# MicroSD.net
KiCad netlist of a schematic drawn in Altium Designer
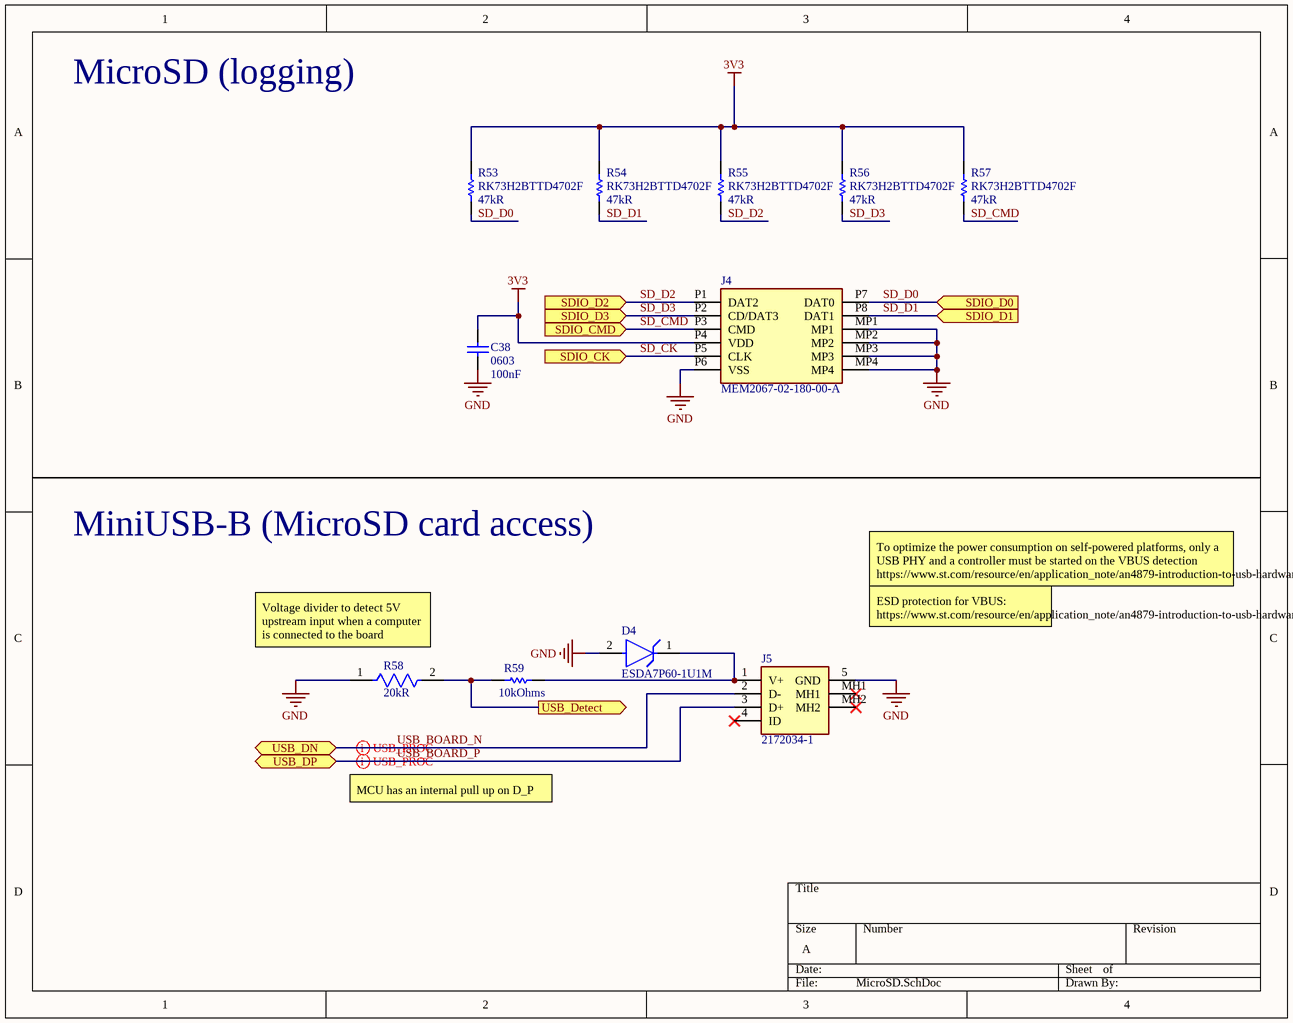
[diagram p0: MicroSD.SchDoc]

(export (version "E")
  (design (tool "Eeschema 10.0.6"))
  (components
    (comp (ref "C38")
      (value "C0603X104K5RACTU")
      (footprint "CAPC1608X87X35NL15T15")
      (fields
        (field (name "MANUFACTURER") "Kemet")
        (field (name "CASE CODE (IMPERIAL)") "0603")
        (field (name "CAPACITANCE") "100nF")
        (field (name "TOLERANCE") "10%")
        (field (name "VOLTAGE") "50V")
      )
      (libsource (lib "Altium Content Vault") (part "CAP"))
    )
    (comp (ref "D4")
      (value "ESDA7P60-1U1M")
      (footprint "FP-1610-MFG")
      (description "TVS DIODE 5V 11.6V 1610")
      (fields
        (field (name "MANUFACTURER") "STMicroelectronics")
        (field (name "OCTOPART") "https://octopart.com/esda7p60-1u1m-stmicroelectronics-52112702")
      )
      (libsource (lib "Altium Content Vault") (part "f813f71cba58e380607f5dd3caf9714"))
    )
    (comp (ref "J4")
      (value "MEM2067-02-180-00-A")
      (footprint "SamacSys:MEM20670218000A")
      (description "Connector")
      (fields (field (name "MOUSER PART NUMBER") "640-MEM20670218000A"))
      (libsource (lib "*") (part "MEM2067-02-180-00-A"))
    )
    (comp (ref "J5")
      (value "2172034-1")
      (footprint "SamacSys:21720341")
      (description "Connector")
      (fields (field (name "MOUSER PART NUMBER") "571-2172034-1"))
      (libsource (lib "*") (part "2172034-1"))
    )
    (comp (ref "R53")
      (value "RK73H2BTTD4702F")
      (footprint "RESC3216X70X40NL20T20")
      (fields (field (name "MANUFACTURER") "KOA Speer") (field (name "ALTIUM_VALUE") "47kR"))
      (libsource (lib "Altium Content Vault") (part "RES"))
    )
    (comp (ref "R54")
      (value "RK73H2BTTD4702F")
      (footprint "RESC3216X70X40NL20T20")
      (fields (field (name "MANUFACTURER") "KOA Speer") (field (name "ALTIUM_VALUE") "47kR"))
      (libsource (lib "Altium Content Vault") (part "RES"))
    )
    (comp (ref "R55")
      (value "RK73H2BTTD4702F")
      (footprint "RESC3216X70X40NL20T20")
      (fields (field (name "MANUFACTURER") "KOA Speer") (field (name "ALTIUM_VALUE") "47kR"))
      (libsource (lib "Altium Content Vault") (part "RES"))
    )
    (comp (ref "R56")
      (value "RK73H2BTTD4702F")
      (footprint "RESC3216X70X40NL20T20")
      (fields (field (name "MANUFACTURER") "KOA Speer") (field (name "ALTIUM_VALUE") "47kR"))
      (libsource (lib "Altium Content Vault") (part "RES"))
    )
    (comp (ref "R57")
      (value "RK73H2BTTD4702F")
      (footprint "RESC3216X70X40NL20T20")
      (fields (field (name "MANUFACTURER") "KOA Speer") (field (name "ALTIUM_VALUE") "47kR"))
      (libsource (lib "Altium Content Vault") (part "RES"))
    )
    (comp (ref "R58")
      (value "CRCW080520K0JNEB")
      (footprint "FP-CRCW0805-e3-IPC_B")
      (description "RES Thick Film, 20kΩ, 5%, 0.125W, 200ppm/°C, 0805")
      (fields (field (name "RESISTANCE") "20kR") (field (name "TOLERANCE") "5%"))
      (libsource (lib "Altium Content Vault") (part "1029c3af85768c4190bb7ad29bc67b5"))
    )
    (comp (ref "R59")
      (value "RC0603JR-0710KL")
      (footprint "RESC1608X55X25ML10T15")
      (description "Resistor, 10 KOhm, +/- 5%, 100 mW, -55 to 155 degC, 0603 (1608 Metric), RoHS, Tape and Reel")
      (fields
        (field (name "RESISTANCE") "10kOhms")
        (field (name "MANUFACTURER") "Yageo")
        (field (name "TOLERANCE") "5%")
      )
      (libsource (lib "Altium Content Vault") (part "RES-2"))
    )
  )
  (nets
    (net (code "1") (name "/SD_CK") (class "Default")
      (node (ref "J4") (pin "P5") (pinfunction "CLK_P5") (pintype "passive"))
    )
    (net (code "2") (name "/SD_CMD") (class "Default")
      (node (ref "J4") (pin "P3") (pinfunction "CMD_P3") (pintype "passive"))
      (node (ref "R57") (pin "1") (pinfunction "1_1") (pintype "passive"))
    )
    (net (code "3") (name "/SD_D0") (class "Default")
      (node (ref "J4") (pin "P7") (pinfunction "DAT0_P7") (pintype "passive"))
      (node (ref "R53") (pin "1") (pinfunction "1_1") (pintype "passive"))
    )
    (net (code "4") (name "/SD_D1") (class "Default")
      (node (ref "J4") (pin "P8") (pinfunction "DAT1_P8") (pintype "passive"))
      (node (ref "R54") (pin "1") (pinfunction "1_1") (pintype "passive"))
    )
    (net (code "5") (name "/SD_D2") (class "Default")
      (node (ref "J4") (pin "P1") (pinfunction "DAT2_P1") (pintype "passive"))
      (node (ref "R55") (pin "1") (pinfunction "1_1") (pintype "passive"))
    )
    (net (code "6") (name "/SD_D3") (class "Default")
      (node (ref "J4") (pin "P2") (pinfunction "CD/DAT3_P2") (pintype "passive"))
      (node (ref "R56") (pin "1") (pinfunction "1_1") (pintype "passive"))
    )
    (net (code "7") (name "/USB_BOARD_N") (class "Default")
      (node (ref "J5") (pin "2") (pinfunction "D-_2") (pintype "passive"))
    )
    (net (code "8") (name "/USB_BOARD_P") (class "Default")
      (node (ref "J5") (pin "3") (pinfunction "D+_3") (pintype "passive"))
    )
    (net (code "9") (name "/USB_Detect") (class "Default")
      (node (ref "R58") (pin "2") (pinfunction "2_2") (pintype "passive"))
      (node (ref "R59") (pin "1") (pinfunction "1_1") (pintype "passive"))
    )
    (net (code "10") (name "3V3") (class "Default")
      (node (ref "C38") (pin "1") (pinfunction "1_1") (pintype "passive"))
      (node (ref "J4") (pin "P4") (pinfunction "VDD_P4") (pintype "passive"))
      (node (ref "R53") (pin "2") (pinfunction "2_2") (pintype "passive"))
      (node (ref "R54") (pin "2") (pinfunction "2_2") (pintype "passive"))
      (node (ref "R55") (pin "2") (pinfunction "2_2") (pintype "passive"))
      (node (ref "R56") (pin "2") (pinfunction "2_2") (pintype "passive"))
      (node (ref "R57") (pin "2") (pinfunction "2_2") (pintype "passive"))
    )
    (net (code "11") (name "GND") (class "Default")
      (node (ref "C38") (pin "2") (pinfunction "2_2") (pintype "passive"))
      (node (ref "D4") (pin "2") (pinfunction "A_2") (pintype "passive"))
      (node (ref "J4") (pin "MP1") (pinfunction "MP1_MP1") (pintype "passive"))
      (node (ref "J4") (pin "MP2") (pinfunction "MP2_MP2") (pintype "passive"))
      (node (ref "J4") (pin "MP3") (pinfunction "MP3_MP3") (pintype "passive"))
      (node (ref "J4") (pin "MP4") (pinfunction "MP4_MP4") (pintype "passive"))
      (node (ref "J4") (pin "P6") (pinfunction "VSS_P6") (pintype "passive"))
      (node (ref "J5") (pin "5") (pinfunction "GND_5") (pintype "passive"))
      (node (ref "R58") (pin "1") (pinfunction "1_1") (pintype "passive"))
    )
    (net (code "12") (name "Net-(D4-C)") (class "Default")
      (node (ref "D4") (pin "1") (pinfunction "C_1") (pintype "passive"))
      (node (ref "J5") (pin "1") (pinfunction "V+_1") (pintype "passive"))
      (node (ref "R59") (pin "2") (pinfunction "2_2") (pintype "passive"))
    )
    (net (code "13") (name "unconnected-(J5-ID-Pad4)") (class "Default")
      (node (ref "J5") (pin "4") (pinfunction "ID_4") (pintype "passive+no_connect"))
    )
    (net (code "14") (name "unconnected-(J5-PadMH1)") (class "Default")
      (node (ref "J5") (pin "MH1") (pinfunction "MH1_MH1") (pintype "passive+no_connect"))
    )
    (net (code "15") (name "unconnected-(J5-PadMH2)") (class "Default")
      (node (ref "J5") (pin "MH2") (pinfunction "MH2_MH2") (pintype "passive+no_connect"))
    )
  )
)
